# precharge.net
KiCad netlist of a schematic drawn in Altium Designer
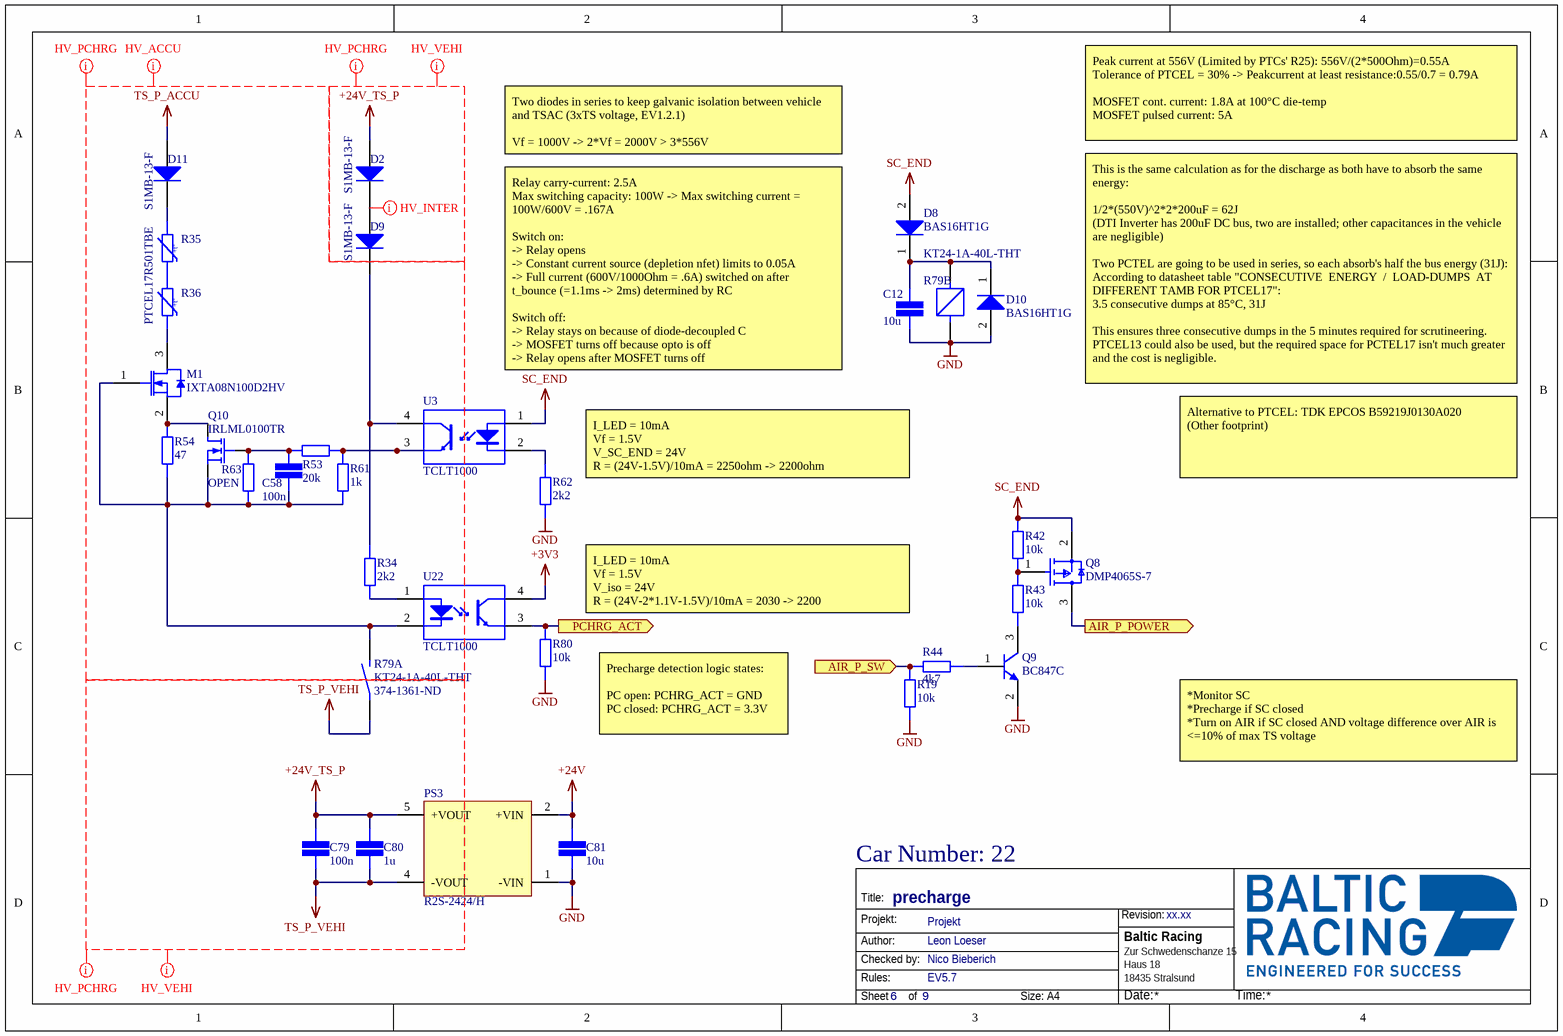
[diagram p0: precharge.SchDoc]

(export (version "E")
  (design (tool "Eeschema 10.0.6"))
  (components
    (comp (ref "C12")
      (value "10u")
      (footprint "CAP 1206/3216")
      (description "Capacitor with multiple Footprints")
      (fields (field (name "VOLTAGE") "25V") (field (name "Comment") "SMD Capacitor"))
      (libsource (lib "") (part "SMD Capacitor_2"))
    )
    (comp (ref "C58")
      (value "100n")
      (footprint "CAP 0603/1608")
      (description "Capacitor with multiple Footprints")
      (fields (field (name "VOLTAGE") "6.3V") (field (name "Comment") "SMD Capacitor"))
      (libsource (lib "Standardbauteile") (part "SMD Capacitor"))
    )
    (comp (ref "C79")
      (value "100n")
      (footprint "CAP 0603/1608")
      (description "Capacitor with multiple Footprints")
      (fields (field (name "VOLTAGE") "6.3V") (field (name "Comment") "SMD Capacitor"))
      (libsource (lib "Standardbauteile") (part "SMD Capacitor"))
    )
    (comp (ref "C80")
      (value "1u")
      (footprint "CAP 0805/2012")
      (description "Capacitor with multiple Footprints")
      (fields (field (name "VOLTAGE") "6.3V") (field (name "Comment") "SMD Capacitor"))
      (libsource (lib "") (part "SMD Capacitor_1"))
    )
    (comp (ref "C81")
      (value "10u")
      (footprint "CAP 1206/3216")
      (description "Capacitor with multiple Footprints")
      (fields (field (name "VOLTAGE") "25V") (field (name "Comment") "SMD Capacitor"))
      (libsource (lib "") (part "SMD Capacitor_3"))
    )
    (comp (ref "D2")
      (value "S1MB-13-F")
      (footprint "DIOD-SMB-2_V")
      (fields (field (name "MANUFACTURER") "Diodes Inc"))
      (libsource (lib "Altium Content Vault") (part "D-AK-2"))
    )
    (comp (ref "D8")
      (value "BAS16HT1G")
      (footprint "ONSC-SOD-323-2-477-02_V")
      (description "Switching Diode, 2-Pin SOD-323, Pb-Free, Tape and Reel")
      (fields (field (name "MANUFACTURER") "On Semiconductor"))
      (libsource (lib "Altium Content Vault") (part "ONSC-D-K1A2-2"))
    )
    (comp (ref "D9")
      (value "S1MB-13-F")
      (footprint "DIOD-SMB-2_V")
      (fields (field (name "MANUFACTURER") "Diodes Inc"))
      (libsource (lib "Altium Content Vault") (part "D-AK-2"))
    )
    (comp (ref "D10")
      (value "BAS16HT1G")
      (footprint "ONSC-SOD-323-2-477-02_V")
      (description "Switching Diode, 2-Pin SOD-323, Pb-Free, Tape and Reel")
      (fields (field (name "MANUFACTURER") "On Semiconductor"))
      (libsource (lib "Altium Content Vault") (part "ONSC-D-K1A2-2"))
    )
    (comp (ref "D11")
      (value "S1MB-13-F")
      (footprint "DIOD-SMB-2_V")
      (fields (field (name "MANUFACTURER") "Diodes Inc"))
      (libsource (lib "Altium Content Vault") (part "D-AK-2"))
    )
    (comp (ref "M1")
      (value "IXTA08N100D2HV")
      (footprint "IXYS_TO-263HV")
      (description "D2 Series - 100V - 1700V N-Channel Depletion Mode Power MOSFETs, TO-263HV, RoHS")
      (fields (field (name "MANUFACTURER") "Littelfuse"))
      (libsource (lib "Leon") (part "IXTA08N100D2HV"))
    )
    (comp (ref "PS3")
      (value "R2S-2424/H")
      (footprint "RECOM_R2S")
      (description "2W DC/DC-Converter 'ECONOLINE' SMD 3kV unreg; V. In: 24; V. Out: 24; mA. Out: 83")
      (fields (field (name "MANUFACTURER") "Recom"))
      (libsource (lib "Leon") (part "R2S-2424/H"))
    )
    (comp (ref "Q8")
      (value "DMP4065S-7")
      (footprint "FP-SOT23-MFG")
      (description "MOSFET P-CH 40V 2.4A SOT23")
      (fields
        (field (name "MANUFACTURER") "Diodes Inc.")
        (field (name "OCTOPART") "https://octopart.com/dmp4065s-7-diodes+inc.-57605044")
      )
      (libsource (lib "Altium Content Vault") (part "90d26376f95f59a583a7107ec0b7fdb"))
    )
    (comp (ref "Q9")
      (value "BC847C")
      (footprint "INF-SOT23_L")
      (description "NPN Silicon AF Transistor, 45 V VCEO, 100 mA IC, SOT23, Reel, Green")
      (fields (field (name "MANUFACTURER") "Infineon"))
      (libsource (lib "Altium Content Vault") (part "INF-BJTNPN-BEC-3"))
    )
    (comp (ref "Q10")
      (value "IRLML0100TR")
      (footprint "SOT23")
      (libsource (lib "Standardbauteile") (part "MOSFET N"))
    )
    (comp (ref "R19")
      (value "10k")
      (footprint "STACKPOLE CSR0603")
      (description "Resistor with multiple footprints")
      (fields (field (name "Comment") "SMD Resistor"))
      (libsource (lib "Standardbauteile") (part "SMD Resistor"))
    )
    (comp (ref "R34")
      (value "2k2")
      (footprint "STACKPOLE CSR0603")
      (description "Resistor with multiple footprints")
      (fields (field (name "Comment") "SMD Resistor"))
      (libsource (lib "Standardbauteile") (part "SMD Resistor"))
    )
    (comp (ref "R35")
      (value "PTCEL17R501TBE")
      (footprint "PTCEL17")
      (description "PTCEL Series 1000 V 500 Ohm ±30 % Radial Inrush Current Limiter PTC Thermistor")
      (fields (field (name "MANUFACTURER") "Vishay BCcomponents") (field (name "TOLERANCE") "30%"))
      (libsource (lib "Leon") (part "PTCEL17R501TBE"))
    )
    (comp (ref "R36")
      (value "PTCEL17R501TBE")
      (footprint "PTCEL17")
      (description "PTCEL Series 1000 V 500 Ohm ±30 % Radial Inrush Current Limiter PTC Thermistor")
      (fields (field (name "MANUFACTURER") "Vishay BCcomponents") (field (name "TOLERANCE") "30%"))
      (libsource (lib "Leon") (part "PTCEL17R501TBE"))
    )
    (comp (ref "R42")
      (value "10k")
      (footprint "STACKPOLE CSR0603")
      (description "Resistor with multiple footprints")
      (fields (field (name "Comment") "SMD Resistor"))
      (libsource (lib "Standardbauteile") (part "SMD Resistor"))
    )
    (comp (ref "R43")
      (value "10k")
      (footprint "STACKPOLE CSR0603")
      (description "Resistor with multiple footprints")
      (fields (field (name "Comment") "SMD Resistor"))
      (libsource (lib "Standardbauteile") (part "SMD Resistor"))
    )
    (comp (ref "R44")
      (value "4k7")
      (footprint "STACKPOLE CSR0603")
      (description "Resistor with multiple footprints")
      (fields (field (name "Comment") "SMD Resistor"))
      (libsource (lib "Standardbauteile") (part "SMD Resistor"))
    )
    (comp (ref "R53")
      (value "20k")
      (footprint "STACKPOLE CSR0603")
      (description "Resistor with multiple footprints")
      (fields (field (name "Comment") "SMD Resistor"))
      (libsource (lib "Standardbauteile") (part "SMD Resistor"))
    )
    (comp (ref "R54")
      (value "47")
      (footprint "STACKPOLE CSR0603")
      (description "Resistor with multiple footprints")
      (fields (field (name "Comment") "SMD Resistor"))
      (libsource (lib "Standardbauteile") (part "SMD Resistor"))
    )
    (comp (ref "R61")
      (value "1k")
      (footprint "STACKPOLE CSR0603")
      (description "Resistor with multiple footprints")
      (fields (field (name "Comment") "SMD Resistor"))
      (libsource (lib "Standardbauteile") (part "SMD Resistor"))
    )
    (comp (ref "R62")
      (value "2k2")
      (footprint "STACKPOLE CSR0603")
      (description "Resistor with multiple footprints")
      (fields (field (name "Comment") "SMD Resistor"))
      (libsource (lib "Standardbauteile") (part "SMD Resistor"))
    )
    (comp (ref "R63")
      (value "OPEN")
      (footprint "STACKPOLE CSR0603")
      (description "Resistor with multiple footprints")
      (fields (field (name "Comment") "SMD Resistor"))
      (libsource (lib "Standardbauteile") (part "SMD Resistor"))
    )
    (comp (ref "R79")
      (value "KT24-1A-40L-THT")
      (footprint "STANDEX_KT_THT")
      (description "Reed Relay, Kt Series, 24 Vdc, 1.8 Kohm, 1 A, 1 Kv, Spst-No Rohs Compliant: Yes")
      (fields
        (field (name "MANUFACTURER") "Standex-Meder Electronics")
        (field (name "SUPPLIER PART NUMBER 1") "374-1361-ND")
      )
      (libsource (lib "") (part "STANDEX_KT24-1A-40L-THT_1"))
    )
    (comp (ref "R80")
      (value "10k")
      (footprint "STACKPOLE CSR0603")
      (description "Resistor with multiple footprints")
      (fields (field (name "Comment") "SMD Resistor"))
      (libsource (lib "Standardbauteile") (part "SMD Resistor"))
    )
    (comp (ref "U3")
      (value "TCLT1000")
      (footprint "VISH-SOP4L-4_V")
      (fields (field (name "MANUFACTURER") "Vishay/Semiconductor"))
      (libsource (lib "Altium Content Vault") (part "OPTO-ACEC-4"))
    )
    (comp (ref "U22")
      (value "TCLT1000")
      (footprint "VISH-SOP4L-4_V")
      (fields (field (name "MANUFACTURER") "Vishay/Semiconductor"))
      (libsource (lib "Altium Content Vault") (part "OPTO-ACEC-4"))
    )
  )
  (nets
    (net (code "1") (name "+3V3") (class "Default")
      (node (ref "U22") (pin "4") (pinfunction "C_4") (pintype "passive"))
    )
    (net (code "2") (name "+24V") (class "Default")
      (node (ref "C81") (pin "2") (pinfunction "2_2") (pintype "passive"))
      (node (ref "PS3") (pin "2") (pinfunction "+VIN_2") (pintype "power_in"))
    )
    (net (code "3") (name "+24V_TS_P") (class "Default")
      (node (ref "C79") (pin "1") (pinfunction "1_1") (pintype "passive"))
      (node (ref "C80") (pin "1") (pinfunction "1_1") (pintype "passive"))
      (node (ref "D2") (pin "1") (pinfunction "A_1") (pintype "passive"))
      (node (ref "PS3") (pin "5") (pinfunction "+VOUT_5") (pintype "power_in"))
    )
    (net (code "4") (name "/AIR_P_POWER") (class "Default")
      (node (ref "Q8") (pin "3") (pinfunction "D_3") (pintype "passive"))
    )
    (net (code "5") (name "/AIR_P_SW") (class "Default")
      (node (ref "R19") (pin "1") (pinfunction "1_1") (pintype "passive"))
      (node (ref "R44") (pin "2") (pinfunction "2_2") (pintype "passive"))
    )
    (net (code "6") (name "/PCHRG_ACT") (class "Default")
      (node (ref "R80") (pin "2") (pinfunction "2_2") (pintype "passive"))
      (node (ref "U22") (pin "3") (pinfunction "E_3") (pintype "passive"))
    )
    (net (code "7") (name "GND") (class "Default")
      (node (ref "C12") (pin "1") (pinfunction "1_1") (pintype "passive"))
      (node (ref "C81") (pin "1") (pinfunction "1_1") (pintype "passive"))
      (node (ref "D10") (pin "2") (pinfunction "A_2") (pintype "passive"))
      (node (ref "PS3") (pin "1") (pinfunction "-VIN_1") (pintype "power_in"))
      (node (ref "Q9") (pin "2") (pinfunction "E_2") (pintype "passive"))
      (node (ref "R19") (pin "2") (pinfunction "2_2") (pintype "passive"))
      (node (ref "R62") (pin "1") (pinfunction "1_1") (pintype "passive"))
      (node (ref "R79") (pin "4") (pinfunction "L2_4") (pintype "passive"))
      (node (ref "R80") (pin "1") (pinfunction "1_1") (pintype "passive"))
    )
    (net (code "8") (name "Net-(D2-K)") (class "Default")
      (node (ref "D2") (pin "2") (pinfunction "K_2") (pintype "passive"))
      (node (ref "D9") (pin "1") (pinfunction "A_1") (pintype "passive"))
    )
    (net (code "9") (name "Net-(D9-K)") (class "Default")
      (node (ref "D9") (pin "2") (pinfunction "K_2") (pintype "passive"))
      (node (ref "R34") (pin "2") (pinfunction "2_2") (pintype "passive"))
      (node (ref "U3") (pin "4") (pinfunction "C_4") (pintype "passive"))
    )
    (net (code "10") (name "Net-(D10-K)") (class "Default")
      (node (ref "C12") (pin "2") (pinfunction "2_2") (pintype "passive"))
      (node (ref "D10") (pin "1") (pinfunction "K_1") (pintype "passive"))
      (node (ref "D8") (pin "1") (pinfunction "K_1") (pintype "passive"))
      (node (ref "R79") (pin "3") (pinfunction "L1_3") (pintype "passive"))
    )
    (net (code "11") (name "Net-(D11-K)") (class "Default")
      (node (ref "D11") (pin "2") (pinfunction "K_2") (pintype "passive"))
      (node (ref "R35") (pin "1") (pinfunction "1_1") (pintype "passive"))
    )
    (net (code "12") (name "Net-(M1-DRAIN)") (class "Default")
      (node (ref "M1") (pin "3") (pinfunction "DRAIN_3") (pintype "passive"))
      (node (ref "R36") (pin "2") (pinfunction "2_2") (pintype "passive"))
    )
    (net (code "13") (name "Net-(M1-GATE)") (class "Default")
      (node (ref "C58") (pin "2") (pinfunction "2_2") (pintype "passive"))
      (node (ref "M1") (pin "1") (pinfunction "GATE_1") (pintype "passive"))
      (node (ref "Q10") (pin "2") (pinfunction "S_2") (pintype "passive"))
      (node (ref "R54") (pin "1") (pinfunction "1_1") (pintype "passive"))
      (node (ref "R61") (pin "1") (pinfunction "1_1") (pintype "passive"))
      (node (ref "R63") (pin "1") (pinfunction "1_1") (pintype "passive"))
      (node (ref "R79") (pin "2") (pinfunction "NO_2") (pintype "passive"))
      (node (ref "U22") (pin "2") (pinfunction "C_2") (pintype "passive"))
    )
    (net (code "14") (name "Net-(M1-SOURCE)") (class "Default")
      (node (ref "M1") (pin "2") (pinfunction "SOURCE_2") (pintype "passive"))
      (node (ref "Q10") (pin "3") (pinfunction "D_3") (pintype "passive"))
      (node (ref "R54") (pin "2") (pinfunction "2_2") (pintype "passive"))
    )
    (net (code "15") (name "Net-(Q8-G)") (class "Default")
      (node (ref "Q8") (pin "1") (pinfunction "G_1") (pintype "passive"))
      (node (ref "R42") (pin "2") (pinfunction "2_2") (pintype "passive"))
      (node (ref "R43") (pin "1") (pinfunction "1_1") (pintype "passive"))
    )
    (net (code "16") (name "Net-(Q9-B)") (class "Default")
      (node (ref "Q9") (pin "1") (pinfunction "B_1") (pintype "passive"))
      (node (ref "R44") (pin "1") (pinfunction "1_1") (pintype "passive"))
    )
    (net (code "17") (name "Net-(Q9-C)") (class "Default")
      (node (ref "Q9") (pin "3") (pinfunction "C_3") (pintype "passive"))
      (node (ref "R43") (pin "2") (pinfunction "2_2") (pintype "passive"))
    )
    (net (code "18") (name "Net-(Q10-G)") (class "Default")
      (node (ref "C58") (pin "1") (pinfunction "1_1") (pintype "passive"))
      (node (ref "Q10") (pin "1") (pinfunction "G_1") (pintype "passive"))
      (node (ref "R53") (pin "2") (pinfunction "2_2") (pintype "passive"))
      (node (ref "R63") (pin "2") (pinfunction "2_2") (pintype "passive"))
    )
    (net (code "19") (name "Net-(R35-Pad2)") (class "Default")
      (node (ref "R35") (pin "2") (pinfunction "2_2") (pintype "passive"))
      (node (ref "R36") (pin "1") (pinfunction "1_1") (pintype "passive"))
    )
    (net (code "20") (name "Net-(R62-Pad2)") (class "Default")
      (node (ref "R62") (pin "2") (pinfunction "2_2") (pintype "passive"))
      (node (ref "U3") (pin "2") (pinfunction "C_2") (pintype "passive"))
    )
    (net (code "21") (name "Net-(U3-E)") (class "Default")
      (node (ref "R53") (pin "1") (pinfunction "1_1") (pintype "passive"))
      (node (ref "R61") (pin "2") (pinfunction "2_2") (pintype "passive"))
      (node (ref "U3") (pin "3") (pinfunction "E_3") (pintype "passive"))
    )
    (net (code "22") (name "Net-(U22-A)") (class "Default")
      (node (ref "R34") (pin "1") (pinfunction "1_1") (pintype "passive"))
      (node (ref "U22") (pin "1") (pinfunction "A_1") (pintype "passive"))
    )
    (net (code "23") (name "SC_END") (class "Default")
      (node (ref "D8") (pin "2") (pinfunction "A_2") (pintype "passive"))
      (node (ref "Q8") (pin "2") (pinfunction "S_2") (pintype "passive"))
      (node (ref "R42") (pin "1") (pinfunction "1_1") (pintype "passive"))
      (node (ref "U3") (pin "1") (pinfunction "A_1") (pintype "passive"))
    )
    (net (code "24") (name "TS_P_ACCU") (class "Default")
      (node (ref "D11") (pin "1") (pinfunction "A_1") (pintype "passive"))
    )
    (net (code "25") (name "TS_P_VEHI") (class "Default")
      (node (ref "C79") (pin "2") (pinfunction "2_2") (pintype "passive"))
      (node (ref "C80") (pin "2") (pinfunction "2_2") (pintype "passive"))
      (node (ref "PS3") (pin "4") (pinfunction "-VOUT_4") (pintype "power_in"))
      (node (ref "R79") (pin "1") (pinfunction "COM_1") (pintype "passive"))
    )
  )
)
